# 03_EINK.net
KiCad netlist of a schematic drawn in Altium Designer
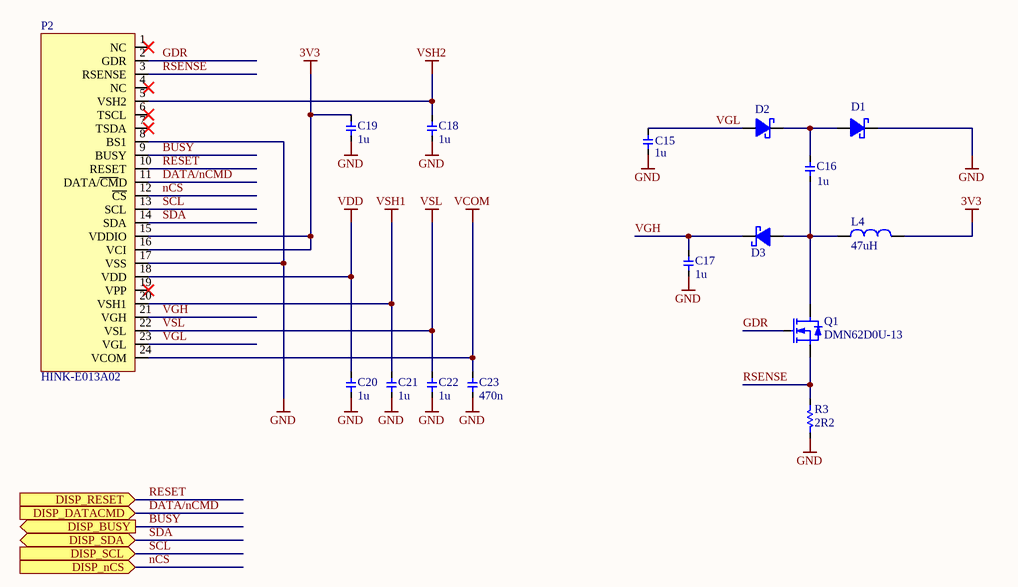
[diagram p0: 03_EINK.SchDoc]

(export (version "E")
  (design (tool "Eeschema 10.0.6"))
  (components
    (comp (ref "C15")
      (value "1u")
      (footprint "Moji Footprintovi:0603 - CAP HS")
      (description "Capacitor")
      (fields
        (field (name "MANUFACTURER") "Samsung Electro-Mechanics")
        (field (name "MANUFACTURER PART NUMBER") "CL10B105KA8VPNC")
      )
      (libsource (lib "Moji Schematici (1)") (part "Cap"))
    )
    (comp (ref "C16")
      (value "1u")
      (footprint "Moji Footprintovi:0603 - CAP HS")
      (description "Capacitor")
      (fields
        (field (name "MANUFACTURER") "Samsung Electro-Mechanics")
        (field (name "MANUFACTURER PART NUMBER") "CL10B105KA8VPNC")
      )
      (libsource (lib "Moji Schematici (1)") (part "Cap"))
    )
    (comp (ref "C17")
      (value "1u")
      (footprint "Moji Footprintovi:0603 - CAP HS")
      (description "Capacitor")
      (fields
        (field (name "MANUFACTURER") "Samsung Electro-Mechanics")
        (field (name "MANUFACTURER PART NUMBER") "CL10B105KA8VPNC")
      )
      (libsource (lib "Moji Schematici (1)") (part "Cap"))
    )
    (comp (ref "C18")
      (value "1u")
      (footprint "Moji Footprintovi:0603 - CAP HS")
      (description "Capacitor")
      (fields
        (field (name "MANUFACTURER") "Samsung Electro-Mechanics")
        (field (name "MANUFACTURER PART NUMBER") "CL10B105KA8VPNC")
      )
      (libsource (lib "Moji Schematici (1)") (part "Cap"))
    )
    (comp (ref "C19")
      (value "1u")
      (footprint "Moji Footprintovi:0603 - CAP HS")
      (description "Capacitor")
      (fields
        (field (name "MANUFACTURER") "Samsung Electro-Mechanics")
        (field (name "MANUFACTURER PART NUMBER") "CL10B105KA8VPNC")
      )
      (libsource (lib "Moji Schematici (1)") (part "Cap"))
    )
    (comp (ref "C20")
      (value "1u")
      (footprint "Moji Footprintovi:0603 - CAP HS")
      (description "Capacitor")
      (fields
        (field (name "MANUFACTURER") "Samsung Electro-Mechanics")
        (field (name "MANUFACTURER PART NUMBER") "CL10B105KA8VPNC")
      )
      (libsource (lib "Moji Schematici (1)") (part "Cap"))
    )
    (comp (ref "C21")
      (value "1u")
      (footprint "Moji Footprintovi:0603 - CAP HS")
      (description "Capacitor")
      (fields
        (field (name "MANUFACTURER") "Samsung Electro-Mechanics")
        (field (name "MANUFACTURER PART NUMBER") "CL10B105KA8VPNC")
      )
      (libsource (lib "Moji Schematici (1)") (part "Cap"))
    )
    (comp (ref "C22")
      (value "1u")
      (footprint "Moji Footprintovi:0603 - CAP HS")
      (description "Capacitor")
      (fields
        (field (name "MANUFACTURER") "Samsung Electro-Mechanics")
        (field (name "MANUFACTURER PART NUMBER") "CL10B105KA8VPNC")
      )
      (libsource (lib "Moji Schematici (1)") (part "Cap"))
    )
    (comp (ref "C23")
      (value "470n")
      (footprint "Moji Footprintovi:0603 - CAP HS")
      (description "Capacitor")
      (fields
        (field (name "MANUFACTURER") "Samsung Electro-Mechanics")
        (field (name "MANUFACTURER PART NUMBER") "CL10B474KA8NNNC")
      )
      (libsource (lib "Moji Schematici (1)") (part "Cap"))
    )
    (comp (ref "D1")
      (value "Diode Schotky")
      (footprint "Moji Footprintovi:SOD123F")
      (fields
        (field (name "MANUFACTURER") "onsemi")
        (field (name "MANUFACTURER PART NUMBER") "NRVB130LSFT1G")
        (field (name "DISTRIBUTOR PART NUMBER") "NRVB130LSFT1GOSCT-ND")
      )
      (libsource (lib "Moji Schematici (1)") (part "Diode Schotky"))
    )
    (comp (ref "D2")
      (value "Diode Schotky")
      (footprint "Moji Footprintovi:SOD123F")
      (fields
        (field (name "MANUFACTURER") "onsemi")
        (field (name "MANUFACTURER PART NUMBER") "NRVB130LSFT1G")
        (field (name "DISTRIBUTOR PART NUMBER") "NRVB130LSFT1GOSCT-ND")
      )
      (libsource (lib "Moji Schematici (1)") (part "Diode Schotky"))
    )
    (comp (ref "D3")
      (value "Diode Schotky")
      (footprint "Moji Footprintovi:SOD123F")
      (fields
        (field (name "MANUFACTURER") "onsemi")
        (field (name "MANUFACTURER PART NUMBER") "NRVB130LSFT1G")
        (field (name "DISTRIBUTOR PART NUMBER") "NRVB130LSFT1GOSCT-ND")
      )
      (libsource (lib "Moji Schematici (1)") (part "Diode Schotky"))
    )
    (comp (ref "L4")
      (value "47uH")
      (footprint "Moji Footprintovi:IND_5050")
      (description "Inductor")
      (fields
        (field (name "MANUFACTURER") "TDK Corporation")
        (field (name "MANUFACTURER PART NUMBER") "VLCF5024T-470MR40-2")
      )
      (libsource (lib "Moji Schematici (1)") (part "Inductor"))
    )
    (comp (ref "P2")
      (value "HINK-E013A02")
      (footprint "Moji Footprintovi:SFV24R-1STE1HLF")
      (fields
        (field (name "DISTRIBUTOR PART NUMBER") "609-SFV24R-4STE1HLFCT-ND")
        (field (name "MANUFACTURER") "Amphenol ICC (FCI)")
        (field (name "MANUFACTURER PART NUMBER") "SFV24R-4STE1HLF")
      )
      (libsource (lib "Moji Schematici (1)") (part "SFV24R-1STE1HLF"))
    )
    (comp (ref "Q1")
      (value "DMN62D0U-13")
      (footprint "Moji Footprintovi:SOT90P240X100-3N")
      (description "MOSFET N-CH 60V 0.38A")
      (fields
        (field (name "MANUFACTURER") "Diodes Incorporated")
        (field (name "DISTRIBUTOR PART NUMBER") "DMN62D0U-13DICT-ND")
      )
      (libsource (lib "Moji Schematici (1)") (part "DMN62D0U-13"))
    )
    (comp (ref "R3")
      (value "2R2")
      (footprint "Footprint_Misc:0603 - HS")
      (description "Resistor")
      (fields (field (name "DISTRIBUTOR PART NUMBER") "311-2.2HRCT-ND") (field (name "MANUFACTURER") "YAGEO"))
      (libsource (lib "Moji Schematici (1)") (part "Res"))
    )
  )
  (nets
    (net (code "1") (name "/BUSY") (class "Default")
      (node (ref "P2") (pin "9") (pinfunction "BUSY_9") (pintype "passive"))
    )
    (net (code "2") (name "/DATA{slash}nCMD") (class "Default")
      (node (ref "P2") (pin "11") (pinfunction "DATA/~{CM}D_11") (pintype "passive"))
    )
    (net (code "3") (name "/GDR") (class "Default")
      (node (ref "P2") (pin "2") (pinfunction "GDR_2") (pintype "passive"))
      (node (ref "Q1") (pin "1") (pinfunction "G_1") (pintype "passive"))
    )
    (net (code "4") (name "/RESET") (class "Default")
      (node (ref "P2") (pin "10") (pinfunction "RESET_10") (pintype "passive"))
    )
    (net (code "5") (name "/RSENSE") (class "Default")
      (node (ref "P2") (pin "3") (pinfunction "RSENSE_3") (pintype "passive"))
      (node (ref "Q1") (pin "2") (pinfunction "S_2") (pintype "passive"))
      (node (ref "R3") (pin "1") (pinfunction "1_1") (pintype "passive"))
    )
    (net (code "6") (name "/SCL") (class "Default")
      (node (ref "P2") (pin "13") (pinfunction "SCL_13") (pintype "passive"))
    )
    (net (code "7") (name "/SDA") (class "Default")
      (node (ref "P2") (pin "14") (pinfunction "SDA_14") (pintype "passive"))
    )
    (net (code "8") (name "/VGH") (class "Default")
      (node (ref "C17") (pin "1") (pinfunction "1_1") (pintype "passive"))
      (node (ref "D3") (pin "K") (pinfunction "K_K") (pintype "passive"))
      (node (ref "P2") (pin "21") (pinfunction "VGH_21") (pintype "passive"))
    )
    (net (code "9") (name "/VGL") (class "Default")
      (node (ref "C15") (pin "1") (pinfunction "1_1") (pintype "passive"))
      (node (ref "D2") (pin "A") (pinfunction "A_A") (pintype "passive"))
      (node (ref "P2") (pin "23") (pinfunction "VGL_23") (pintype "passive"))
    )
    (net (code "10") (name "/nCS") (class "Default")
      (node (ref "P2") (pin "12") (pinfunction "~{CS}_12") (pintype "passive"))
    )
    (net (code "11") (name "3V3") (class "Default")
      (node (ref "C19") (pin "2") (pinfunction "2_2") (pintype "passive"))
      (node (ref "L4") (pin "1") (pinfunction "1_1") (pintype "passive"))
      (node (ref "P2") (pin "15") (pinfunction "VDDIO_15") (pintype "passive"))
      (node (ref "P2") (pin "16") (pinfunction "VCI_16") (pintype "passive"))
    )
    (net (code "12") (name "GND") (class "Default")
      (node (ref "C15") (pin "2") (pinfunction "2_2") (pintype "passive"))
      (node (ref "C17") (pin "2") (pinfunction "2_2") (pintype "passive"))
      (node (ref "C18") (pin "1") (pinfunction "1_1") (pintype "passive"))
      (node (ref "C19") (pin "1") (pinfunction "1_1") (pintype "passive"))
      (node (ref "C20") (pin "1") (pinfunction "1_1") (pintype "passive"))
      (node (ref "C21") (pin "1") (pinfunction "1_1") (pintype "passive"))
      (node (ref "C22") (pin "1") (pinfunction "1_1") (pintype "passive"))
      (node (ref "C23") (pin "1") (pinfunction "1_1") (pintype "passive"))
      (node (ref "D1") (pin "K") (pinfunction "K_K") (pintype "passive"))
      (node (ref "P2") (pin "17") (pinfunction "VSS_17") (pintype "passive"))
      (node (ref "P2") (pin "8") (pinfunction "BS1_8") (pintype "passive"))
      (node (ref "R3") (pin "2") (pinfunction "2_2") (pintype "passive"))
    )
    (net (code "13") (name "Net-(C16-Pad2)") (class "Default")
      (node (ref "C16") (pin "2") (pinfunction "2_2") (pintype "passive"))
      (node (ref "D1") (pin "A") (pinfunction "A_A") (pintype "passive"))
      (node (ref "D2") (pin "K") (pinfunction "K_K") (pintype "passive"))
    )
    (net (code "14") (name "Net-(Q1-D)") (class "Default")
      (node (ref "C16") (pin "1") (pinfunction "1_1") (pintype "passive"))
      (node (ref "D3") (pin "A") (pinfunction "A_A") (pintype "passive"))
      (node (ref "L4") (pin "2") (pinfunction "2_2") (pintype "passive"))
      (node (ref "Q1") (pin "3") (pinfunction "D_3") (pintype "passive"))
    )
    (net (code "15") (name "VCOM") (class "Default")
      (node (ref "C23") (pin "2") (pinfunction "2_2") (pintype "passive"))
      (node (ref "P2") (pin "24") (pinfunction "VCOM_24") (pintype "passive"))
    )
    (net (code "16") (name "VDD") (class "Default")
      (node (ref "C20") (pin "2") (pinfunction "2_2") (pintype "passive"))
      (node (ref "P2") (pin "18") (pinfunction "VDD_18") (pintype "passive"))
    )
    (net (code "17") (name "VSH1") (class "Default")
      (node (ref "C21") (pin "2") (pinfunction "2_2") (pintype "passive"))
      (node (ref "P2") (pin "20") (pinfunction "VSH1_20") (pintype "passive"))
    )
    (net (code "18") (name "VSH2") (class "Default")
      (node (ref "C18") (pin "2") (pinfunction "2_2") (pintype "passive"))
      (node (ref "P2") (pin "5") (pinfunction "VSH2_5") (pintype "passive"))
    )
    (net (code "19") (name "VSL") (class "Default")
      (node (ref "C22") (pin "2") (pinfunction "2_2") (pintype "passive"))
      (node (ref "P2") (pin "22") (pinfunction "VSL_22") (pintype "passive"))
    )
    (net (code "20") (name "unconnected-(P2-NC-Pad1)") (class "Default")
      (node (ref "P2") (pin "1") (pinfunction "NC_1") (pintype "passive+no_connect"))
    )
    (net (code "21") (name "unconnected-(P2-NC-Pad4)") (class "Default")
      (node (ref "P2") (pin "4") (pinfunction "NC_4") (pintype "passive+no_connect"))
    )
    (net (code "22") (name "unconnected-(P2-TSCL-Pad6)") (class "Default")
      (node (ref "P2") (pin "6") (pinfunction "TSCL_6") (pintype "passive+no_connect"))
    )
    (net (code "23") (name "unconnected-(P2-TSDA-Pad7)") (class "Default")
      (node (ref "P2") (pin "7") (pinfunction "TSDA_7") (pintype "passive+no_connect"))
    )
    (net (code "24") (name "unconnected-(P2-VPP-Pad19)") (class "Default")
      (node (ref "P2") (pin "19") (pinfunction "VPP_19") (pintype "passive+no_connect"))
    )
  )
)
